# source_eagle.net
KiCad netlist of a schematic drawn in EAGLE
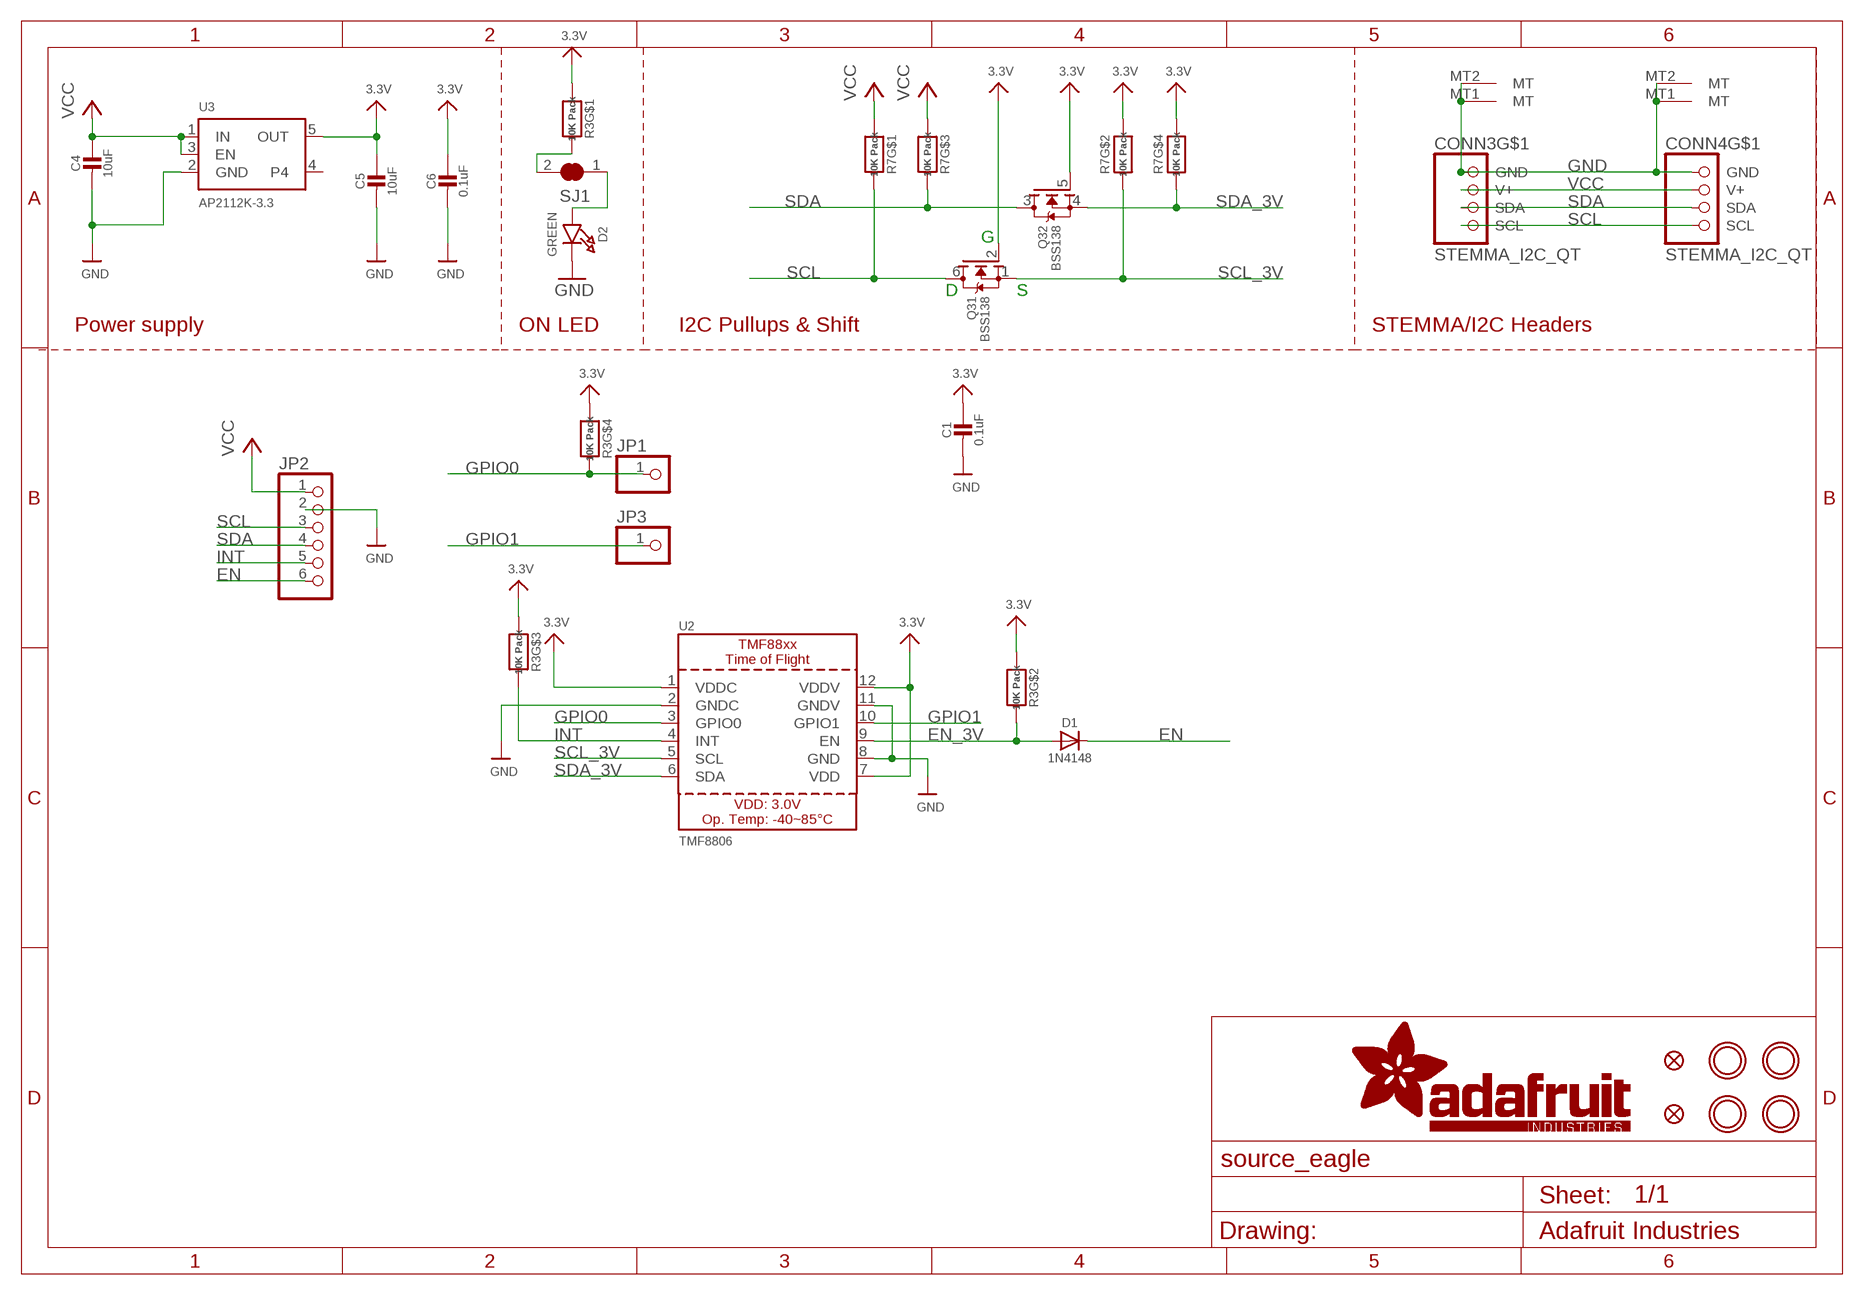
[diagram p0: schematic, sheet 1]

(export (version "E")
  (design (tool "Eeschema 10.0.6"))
  (components
    (comp (ref "C1")
      (value "0.1uF")
      (footprint "eagle-import:0603-NO")
      (libsource (lib "eagle-import") (part "CAP_CERAMIC0603_NO"))
    )
    (comp (ref "C4")
      (value "10uF")
      (footprint "eagle-import:0805-NO")
      (libsource (lib "eagle-import") (part "CAP_CERAMIC0805-NOOUTLINE"))
    )
    (comp (ref "C5")
      (value "10uF")
      (footprint "eagle-import:0805-NO")
      (libsource (lib "eagle-import") (part "CAP_CERAMIC0805-NOOUTLINE"))
    )
    (comp (ref "C6")
      (value "0.1uF")
      (footprint "eagle-import:0603-NO")
      (libsource (lib "eagle-import") (part "CAP_CERAMIC0603_NO"))
    )
    (comp (ref "CONN3")
      (value "STEMMA_I2C_QT")
      (footprint "eagle-import:JST_SH4")
      (libsource (lib "eagle-import") (part "STEMMA_I2C_QT"))
    )
    (comp (ref "CONN4")
      (value "STEMMA_I2C_QT")
      (footprint "eagle-import:JST_SH4")
      (libsource (lib "eagle-import") (part "STEMMA_I2C_QT"))
    )
    (comp (ref "D1")
      (value "1N4148")
      (footprint "eagle-import:SOD-323")
      (libsource (lib "eagle-import") (part "DIODESOD-323"))
    )
    (comp (ref "D2")
      (value "GREEN")
      (footprint "eagle-import:CHIPLED_0603_NOOUTLINE")
      (libsource (lib "eagle-import") (part "LED0603_NOOUTLINE"))
    )
    (comp (ref "FID1")
      (value "FIDUCIAL_0.5MM")
      (footprint "eagle-import:FIDUCIAL_0.5MM")
      (libsource (lib "eagle-import") (part "FIDUCIAL_0.5MM"))
    )
    (comp (ref "FID4")
      (value "FIDUCIAL_0.5MM")
      (footprint "eagle-import:FIDUCIAL_0.5MM")
      (libsource (lib "eagle-import") (part "FIDUCIAL_0.5MM"))
    )
    (comp (ref "JP1")
      (value "HEADER-1X1ROUND")
      (footprint "eagle-import:1X01_ROUND")
      (libsource (lib "eagle-import") (part "HEADER-1X1ROUND"))
    )
    (comp (ref "JP2")
      (value "HEADER-1X670MIL")
      (footprint "eagle-import:1X06_ROUND_70")
      (libsource (lib "eagle-import") (part "HEADER-1X670MIL"))
    )
    (comp (ref "JP3")
      (value "HEADER-1X1ROUND")
      (footprint "eagle-import:1X01_ROUND")
      (libsource (lib "eagle-import") (part "HEADER-1X1ROUND"))
    )
    (comp (ref "Q3")
      (value "BSS138")
      (footprint "eagle-import:SOT363")
      (libsource (lib "eagle-import") (part "MOSFET-N_DUAL"))
    )
    (comp (ref "R3")
      (value "10K Pack")
      (footprint "eagle-import:RESPACK_4X0603")
      (libsource (lib "eagle-import") (part "RESISTOR_4PACK"))
    )
    (comp (ref "R7")
      (value "10K Pack")
      (footprint "eagle-import:RESPACK_4X0603")
      (libsource (lib "eagle-import") (part "RESISTOR_4PACK"))
    )
    (comp (ref "SJ1")
      (value "SOLDERJUMPER_CLOSED")
      (footprint "eagle-import:SOLDERJUMPER_CLOSEDWIRE")
      (libsource (lib "eagle-import") (part "SOLDERJUMPER_CLOSED"))
    )
    (comp (ref "U$30")
      (value "MOUNTINGHOLE2.5")
      (footprint "eagle-import:MOUNTINGHOLE_2.5_PLATED")
      (libsource (lib "eagle-import") (part "MOUNTINGHOLE2.5"))
    )
    (comp (ref "U$31")
      (value "MOUNTINGHOLE2.5")
      (footprint "eagle-import:MOUNTINGHOLE_2.5_PLATED")
      (libsource (lib "eagle-import") (part "MOUNTINGHOLE2.5"))
    )
    (comp (ref "U$33")
      (value "MOUNTINGHOLE2.5")
      (footprint "eagle-import:MOUNTINGHOLE_2.5_PLATED")
      (libsource (lib "eagle-import") (part "MOUNTINGHOLE2.5"))
    )
    (comp (ref "U$34")
      (value "MOUNTINGHOLE2.5")
      (footprint "eagle-import:MOUNTINGHOLE_2.5_PLATED")
      (libsource (lib "eagle-import") (part "MOUNTINGHOLE2.5"))
    )
    (comp (ref "U2")
      (value "TMF8806")
      (footprint "eagle-import:TMF880X")
      (libsource (lib "eagle-import") (part "TMF880X_12"))
    )
    (comp (ref "U3")
      (value "AP2112K-3.3")
      (footprint "eagle-import:SOT23-5")
      (fields (field (name "JLC_ROTATION") "0"))
      (libsource (lib "eagle-import") (part "VREG_SOT23-5"))
    )
  )
  (nets
    (net (code "1") (name "/EN") (class "Default")
      (node (ref "D1") (pin "C") (pinfunction "C_C") (pintype "passive"))
      (node (ref "JP2") (pin "6") (pinfunction "6_6") (pintype "passive"))
    )
    (net (code "2") (name "/EN_3V") (class "Default")
      (node (ref "D1") (pin "A") (pinfunction "A_A") (pintype "passive"))
      (node (ref "R3") (pin "7") (pinfunction "2_7") (pintype "passive"))
      (node (ref "U2") (pin "9") (pinfunction "EN_9") (pintype "bidirectional"))
    )
    (net (code "3") (name "/GPIO0") (class "Default")
      (node (ref "JP1") (pin "1") (pinfunction "1_1") (pintype "passive"))
      (node (ref "R3") (pin "5") (pinfunction "2_5") (pintype "passive"))
      (node (ref "U2") (pin "3") (pinfunction "GPIO0_3") (pintype "bidirectional"))
    )
    (net (code "4") (name "/GPIO1") (class "Default")
      (node (ref "JP3") (pin "1") (pinfunction "1_1") (pintype "passive"))
      (node (ref "U2") (pin "10") (pinfunction "GPIO1_10") (pintype "bidirectional"))
    )
    (net (code "5") (name "/INT") (class "Default")
      (node (ref "JP2") (pin "5") (pinfunction "5_5") (pintype "passive"))
      (node (ref "R3") (pin "6") (pinfunction "2_6") (pintype "passive"))
      (node (ref "U2") (pin "4") (pinfunction "INT_4") (pintype "bidirectional"))
    )
    (net (code "6") (name "/SCL") (class "Default")
      (node (ref "CONN3") (pin "4") (pinfunction "SCL_4") (pintype "passive"))
      (node (ref "CONN4") (pin "4") (pinfunction "SCL_4") (pintype "passive"))
      (node (ref "JP2") (pin "3") (pinfunction "3_3") (pintype "passive"))
      (node (ref "Q3") (pin "6") (pinfunction "D_6") (pintype "bidirectional"))
      (node (ref "R7") (pin "8") (pinfunction "2_8") (pintype "passive"))
    )
    (net (code "7") (name "/SCL_3V") (class "Default")
      (node (ref "Q3") (pin "1") (pinfunction "S_1") (pintype "bidirectional"))
      (node (ref "R7") (pin "7") (pinfunction "2_7") (pintype "passive"))
      (node (ref "U2") (pin "5") (pinfunction "SCL_5") (pintype "input"))
    )
    (net (code "8") (name "/SDA") (class "Default")
      (node (ref "CONN3") (pin "3") (pinfunction "SDA_3") (pintype "passive"))
      (node (ref "CONN4") (pin "3") (pinfunction "SDA_3") (pintype "passive"))
      (node (ref "JP2") (pin "4") (pinfunction "4_4") (pintype "passive"))
      (node (ref "Q3") (pin "3") (pinfunction "D_3") (pintype "bidirectional"))
      (node (ref "R7") (pin "6") (pinfunction "2_6") (pintype "passive"))
    )
    (net (code "9") (name "/SDA_3V") (class "Default")
      (node (ref "Q3") (pin "4") (pinfunction "S_4") (pintype "bidirectional"))
      (node (ref "R7") (pin "5") (pinfunction "2_5") (pintype "passive"))
      (node (ref "U2") (pin "6") (pinfunction "SDA_6") (pintype "bidirectional"))
    )
    (net (code "10") (name "3.3V") (class "Default")
      (node (ref "C1") (pin "1") (pinfunction "1_1") (pintype "passive"))
      (node (ref "C5") (pin "1") (pinfunction "1_1") (pintype "passive"))
      (node (ref "C6") (pin "1") (pinfunction "1_1") (pintype "passive"))
      (node (ref "Q3") (pin "2") (pinfunction "G_2") (pintype "bidirectional"))
      (node (ref "Q3") (pin "5") (pinfunction "G_5") (pintype "bidirectional"))
      (node (ref "R3") (pin "1") (pinfunction "1_1") (pintype "passive"))
      (node (ref "R3") (pin "2") (pinfunction "1_2") (pintype "passive"))
      (node (ref "R3") (pin "3") (pinfunction "1_3") (pintype "passive"))
      (node (ref "R3") (pin "4") (pinfunction "1_4") (pintype "passive"))
      (node (ref "R7") (pin "2") (pinfunction "1_2") (pintype "passive"))
      (node (ref "R7") (pin "4") (pinfunction "1_4") (pintype "passive"))
      (node (ref "U2") (pin "1") (pinfunction "VDDC_1") (pintype "power_in"))
      (node (ref "U2") (pin "12") (pinfunction "VDDV_12") (pintype "power_in"))
      (node (ref "U2") (pin "7") (pinfunction "VDD_7") (pintype "power_in"))
      (node (ref "U3") (pin "5") (pinfunction "OUT_5") (pintype "power_in"))
    )
    (net (code "11") (name "GND") (class "Default")
      (node (ref "C1") (pin "2") (pinfunction "2_2") (pintype "passive"))
      (node (ref "C4") (pin "2") (pinfunction "2_2") (pintype "passive"))
      (node (ref "C5") (pin "2") (pinfunction "2_2") (pintype "passive"))
      (node (ref "C6") (pin "2") (pinfunction "2_2") (pintype "passive"))
      (node (ref "CONN3") (pin "1") (pinfunction "GND_1") (pintype "passive"))
      (node (ref "CONN3") (pin "MT1") (pinfunction "MT_MT1") (pintype "bidirectional"))
      (node (ref "CONN3") (pin "MT2") (pinfunction "MT_MT2") (pintype "bidirectional"))
      (node (ref "CONN4") (pin "1") (pinfunction "GND_1") (pintype "passive"))
      (node (ref "CONN4") (pin "MT1") (pinfunction "MT_MT1") (pintype "bidirectional"))
      (node (ref "CONN4") (pin "MT2") (pinfunction "MT_MT2") (pintype "bidirectional"))
      (node (ref "D2") (pin "C") (pinfunction "C_C") (pintype "passive"))
      (node (ref "JP2") (pin "2") (pinfunction "2_2") (pintype "passive"))
      (node (ref "U2") (pin "11") (pinfunction "GNDV_11") (pintype "power_in"))
      (node (ref "U2") (pin "2") (pinfunction "GNDC_2") (pintype "power_in"))
      (node (ref "U2") (pin "8") (pinfunction "GND_8") (pintype "power_in"))
      (node (ref "U3") (pin "2") (pinfunction "GND_2") (pintype "power_in"))
    )
    (net (code "12") (name "Net-(D2-PadA)") (class "Default")
      (node (ref "D2") (pin "A") (pinfunction "A_A") (pintype "passive"))
      (node (ref "SJ1") (pin "1") (pinfunction "1_1") (pintype "passive"))
    )
    (net (code "13") (name "Net-(R3A-2)") (class "Default")
      (node (ref "R3") (pin "8") (pinfunction "2_8") (pintype "passive"))
      (node (ref "SJ1") (pin "2") (pinfunction "2_2") (pintype "passive"))
    )
    (net (code "14") (name "VCC") (class "Default")
      (node (ref "C4") (pin "1") (pinfunction "1_1") (pintype "passive"))
      (node (ref "CONN3") (pin "2") (pinfunction "V+_2") (pintype "passive"))
      (node (ref "CONN4") (pin "2") (pinfunction "V+_2") (pintype "passive"))
      (node (ref "JP2") (pin "1") (pinfunction "1_1") (pintype "passive"))
      (node (ref "R7") (pin "1") (pinfunction "1_1") (pintype "passive"))
      (node (ref "R7") (pin "3") (pinfunction "1_3") (pintype "passive"))
      (node (ref "U3") (pin "1") (pinfunction "IN_1") (pintype "power_in"))
      (node (ref "U3") (pin "3") (pinfunction "EN_3") (pintype "input"))
    )
    (net (code "15") (name "unconnected-(U3-P4-Pad4)") (class "Default")
      (node (ref "U3") (pin "4") (pinfunction "P4_4") (pintype "bidirectional"))
    )
  )
)
